# S04-INTERFACES.net
KiCad netlist of a schematic drawn in Altium Designer
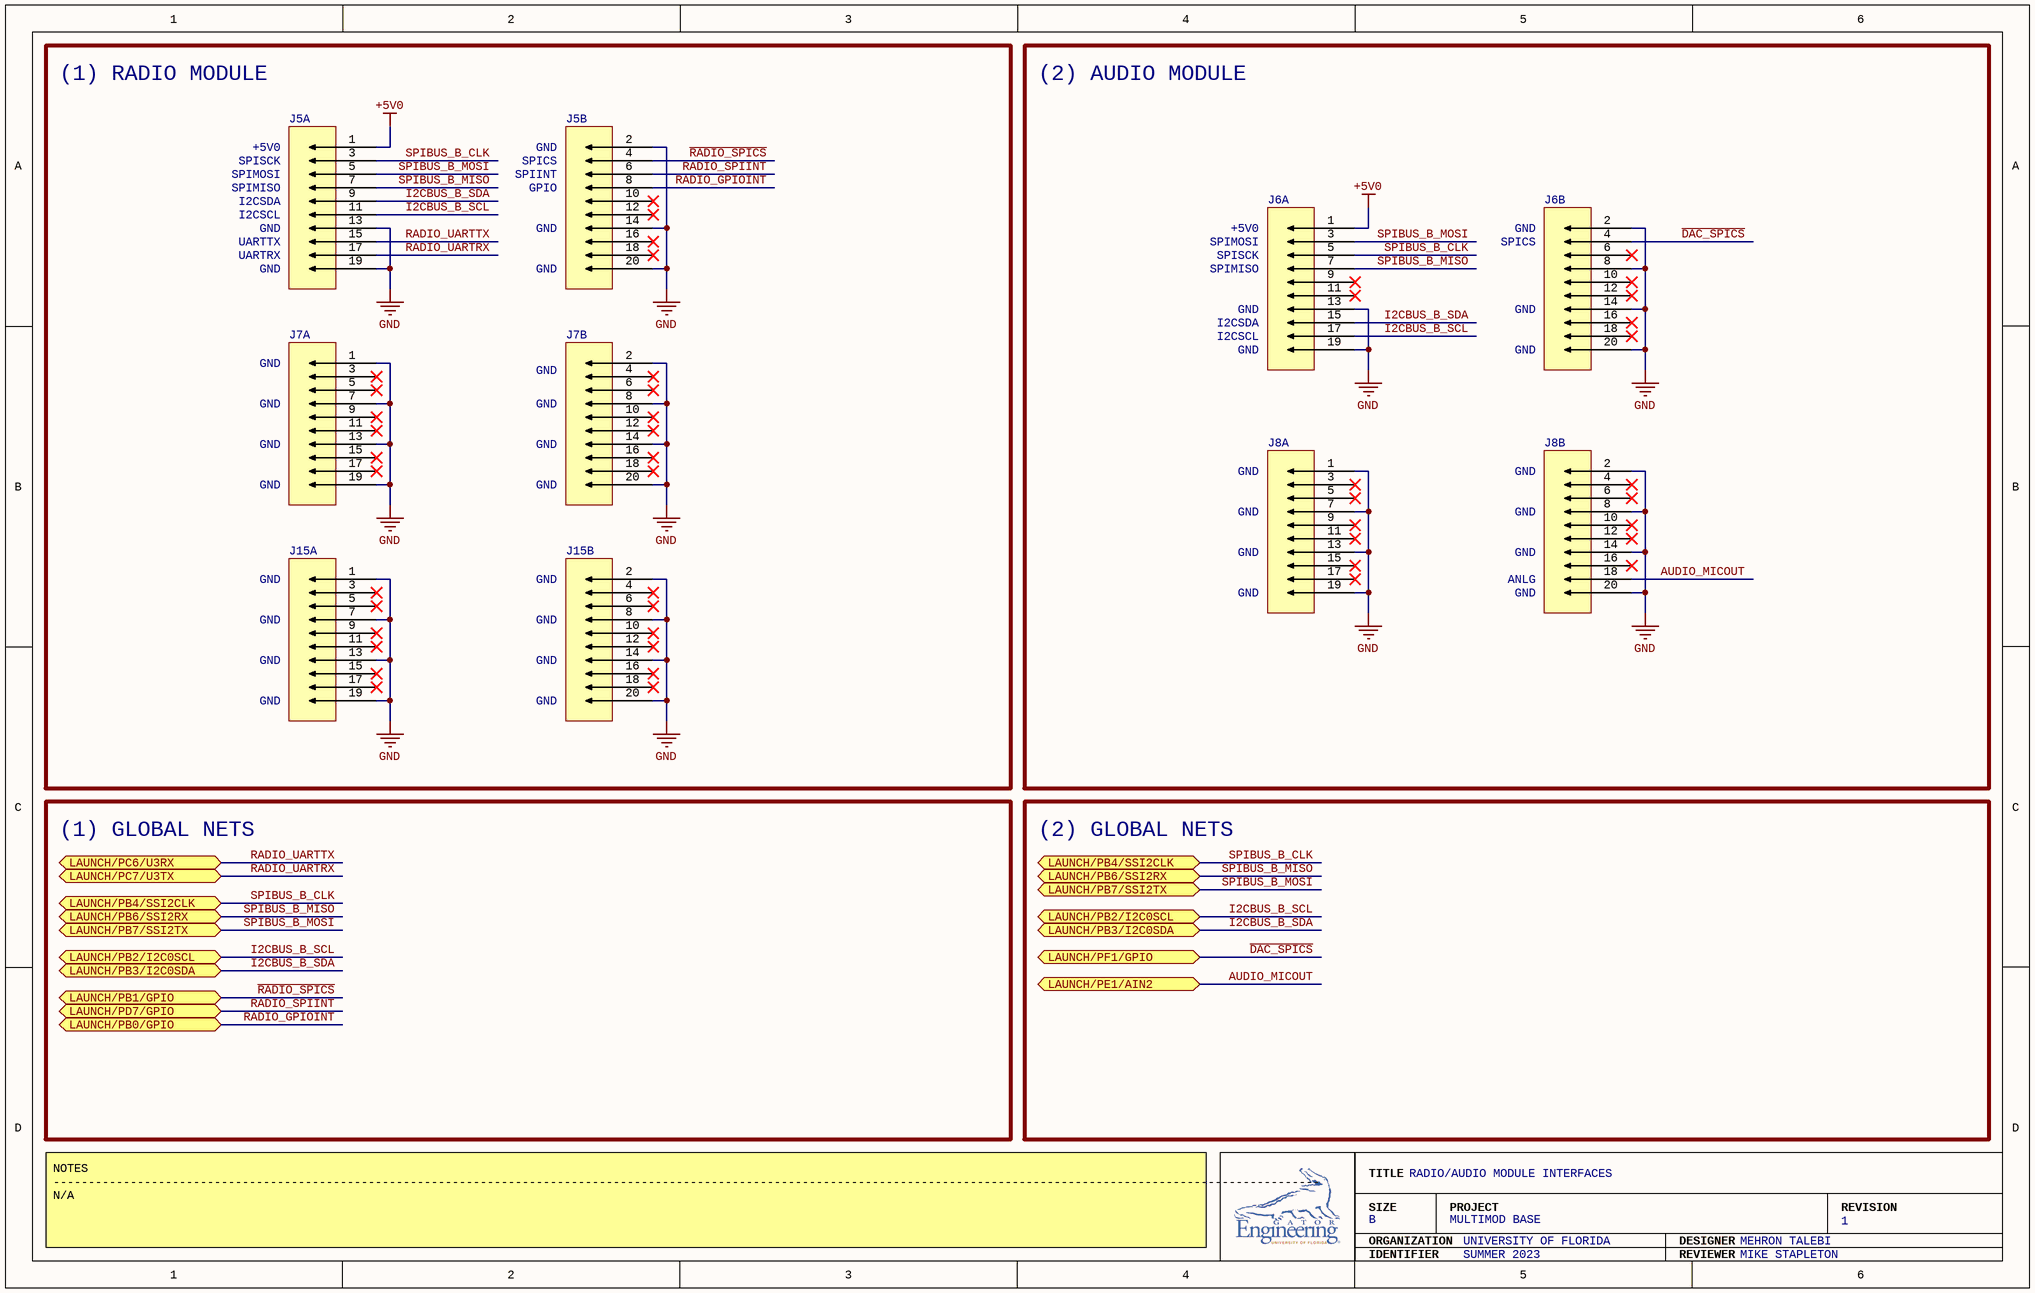
[diagram p0: S04-INTERFACES.SchDoc]

(export (version "E")
  (design (tool "Eeschema 10.0.6"))
  (components
    (comp (ref "J5")
      (value "95278-101-20LF")
      (footprint "95278-101-20LF")
      (description "CONN HEADER SMD 20POS 2.54MM")
      (libsource (lib "Master") (part "95278-101-20LF"))
    )
    (comp (ref "J6")
      (value "95278-101-20LF")
      (footprint "95278-101-20LF")
      (description "CONN HEADER SMD 20POS 2.54MM")
      (libsource (lib "Master") (part "95278-101-20LF"))
    )
    (comp (ref "J7")
      (value "95278-101-20LF")
      (footprint "95278-101-20LF")
      (description "CONN HEADER SMD 20POS 2.54MM")
      (libsource (lib "Master") (part "95278-101-20LF"))
    )
    (comp (ref "J8")
      (value "95278-101-20LF")
      (footprint "95278-101-20LF")
      (description "CONN HEADER SMD 20POS 2.54MM")
      (libsource (lib "Master") (part "95278-101-20LF"))
    )
    (comp (ref "J15")
      (value "95278-101-20LF")
      (footprint "95278-101-20LF")
      (description "CONN HEADER SMD 20POS 2.54MM")
      (libsource (lib "Master") (part "95278-101-20LF"))
    )
  )
  (nets
    (net (code "1") (name "+5V0") (class "Default")
      (node (ref "J5") (pin "1") (pinfunction "1_1") (pintype "passive"))
      (node (ref "J6") (pin "1") (pinfunction "1_1") (pintype "passive"))
    )
    (net (code "2") (name "/AUDIO_MICOUT") (class "Default")
      (node (ref "J8") (pin "18") (pinfunction "18_18") (pintype "passive"))
    )
    (net (code "3") (name "/DAC_SPICS") (class "Default")
      (node (ref "J6") (pin "4") (pinfunction "4_4") (pintype "passive"))
    )
    (net (code "4") (name "/I2CBUS_B_SCL") (class "Default")
      (node (ref "J5") (pin "11") (pinfunction "11_11") (pintype "passive"))
      (node (ref "J6") (pin "17") (pinfunction "17_17") (pintype "passive"))
    )
    (net (code "5") (name "/I2CBUS_B_SDA") (class "Default")
      (node (ref "J5") (pin "9") (pinfunction "9_9") (pintype "passive"))
      (node (ref "J6") (pin "15") (pinfunction "15_15") (pintype "passive"))
    )
    (net (code "6") (name "/RADIO_GPIOINT") (class "Default")
      (node (ref "J5") (pin "8") (pinfunction "8_8") (pintype "passive"))
    )
    (net (code "7") (name "/RADIO_SPICS") (class "Default")
      (node (ref "J5") (pin "4") (pinfunction "4_4") (pintype "passive"))
    )
    (net (code "8") (name "/RADIO_SPIINT") (class "Default")
      (node (ref "J5") (pin "6") (pinfunction "6_6") (pintype "passive"))
    )
    (net (code "9") (name "/RADIO_UARTRX") (class "Default")
      (node (ref "J5") (pin "17") (pinfunction "17_17") (pintype "passive"))
    )
    (net (code "10") (name "/RADIO_UARTTX") (class "Default")
      (node (ref "J5") (pin "15") (pinfunction "15_15") (pintype "passive"))
    )
    (net (code "11") (name "/SPIBUS_B_CLK") (class "Default")
      (node (ref "J5") (pin "3") (pinfunction "3_3") (pintype "passive"))
      (node (ref "J6") (pin "5") (pinfunction "5_5") (pintype "passive"))
    )
    (net (code "12") (name "/SPIBUS_B_MISO") (class "Default")
      (node (ref "J5") (pin "7") (pinfunction "7_7") (pintype "passive"))
      (node (ref "J6") (pin "7") (pinfunction "7_7") (pintype "passive"))
    )
    (net (code "13") (name "/SPIBUS_B_MOSI") (class "Default")
      (node (ref "J5") (pin "5") (pinfunction "5_5") (pintype "passive"))
      (node (ref "J6") (pin "3") (pinfunction "3_3") (pintype "passive"))
    )
    (net (code "14") (name "GND") (class "Default")
      (node (ref "J15") (pin "1") (pinfunction "1_1") (pintype "passive"))
      (node (ref "J15") (pin "13") (pinfunction "13_13") (pintype "passive"))
      (node (ref "J15") (pin "14") (pinfunction "14_14") (pintype "passive"))
      (node (ref "J15") (pin "19") (pinfunction "19_19") (pintype "passive"))
      (node (ref "J15") (pin "2") (pinfunction "2_2") (pintype "passive"))
      (node (ref "J15") (pin "20") (pinfunction "20_20") (pintype "passive"))
      (node (ref "J15") (pin "7") (pinfunction "7_7") (pintype "passive"))
      (node (ref "J15") (pin "8") (pinfunction "8_8") (pintype "passive"))
      (node (ref "J5") (pin "13") (pinfunction "13_13") (pintype "passive"))
      (node (ref "J5") (pin "14") (pinfunction "14_14") (pintype "passive"))
      (node (ref "J5") (pin "19") (pinfunction "19_19") (pintype "passive"))
      (node (ref "J5") (pin "2") (pinfunction "2_2") (pintype "passive"))
      (node (ref "J5") (pin "20") (pinfunction "20_20") (pintype "passive"))
      (node (ref "J6") (pin "13") (pinfunction "13_13") (pintype "passive"))
      (node (ref "J6") (pin "14") (pinfunction "14_14") (pintype "passive"))
      (node (ref "J6") (pin "19") (pinfunction "19_19") (pintype "passive"))
      (node (ref "J6") (pin "2") (pinfunction "2_2") (pintype "passive"))
      (node (ref "J6") (pin "20") (pinfunction "20_20") (pintype "passive"))
      (node (ref "J6") (pin "8") (pinfunction "8_8") (pintype "passive"))
      (node (ref "J7") (pin "1") (pinfunction "1_1") (pintype "passive"))
      (node (ref "J7") (pin "13") (pinfunction "13_13") (pintype "passive"))
      (node (ref "J7") (pin "14") (pinfunction "14_14") (pintype "passive"))
      (node (ref "J7") (pin "19") (pinfunction "19_19") (pintype "passive"))
      (node (ref "J7") (pin "2") (pinfunction "2_2") (pintype "passive"))
      (node (ref "J7") (pin "20") (pinfunction "20_20") (pintype "passive"))
      (node (ref "J7") (pin "7") (pinfunction "7_7") (pintype "passive"))
      (node (ref "J7") (pin "8") (pinfunction "8_8") (pintype "passive"))
      (node (ref "J8") (pin "1") (pinfunction "1_1") (pintype "passive"))
      (node (ref "J8") (pin "13") (pinfunction "13_13") (pintype "passive"))
      (node (ref "J8") (pin "14") (pinfunction "14_14") (pintype "passive"))
      (node (ref "J8") (pin "19") (pinfunction "19_19") (pintype "passive"))
      (node (ref "J8") (pin "2") (pinfunction "2_2") (pintype "passive"))
      (node (ref "J8") (pin "20") (pinfunction "20_20") (pintype "passive"))
      (node (ref "J8") (pin "7") (pinfunction "7_7") (pintype "passive"))
      (node (ref "J8") (pin "8") (pinfunction "8_8") (pintype "passive"))
    )
    (net (code "15") (name "unconnected-(J5-Pad10)") (class "Default")
      (node (ref "J5") (pin "10") (pinfunction "10_10") (pintype "passive+no_connect"))
    )
    (net (code "16") (name "unconnected-(J5-Pad12)") (class "Default")
      (node (ref "J5") (pin "12") (pinfunction "12_12") (pintype "passive+no_connect"))
    )
    (net (code "17") (name "unconnected-(J5-Pad16)") (class "Default")
      (node (ref "J5") (pin "16") (pinfunction "16_16") (pintype "passive+no_connect"))
    )
    (net (code "18") (name "unconnected-(J5-Pad18)") (class "Default")
      (node (ref "J5") (pin "18") (pinfunction "18_18") (pintype "passive+no_connect"))
    )
    (net (code "19") (name "unconnected-(J6-Pad6)") (class "Default")
      (node (ref "J6") (pin "6") (pinfunction "6_6") (pintype "passive+no_connect"))
    )
    (net (code "20") (name "unconnected-(J6-Pad9)") (class "Default")
      (node (ref "J6") (pin "9") (pinfunction "9_9") (pintype "passive+no_connect"))
    )
    (net (code "21") (name "unconnected-(J6-Pad10)") (class "Default")
      (node (ref "J6") (pin "10") (pinfunction "10_10") (pintype "passive+no_connect"))
    )
    (net (code "22") (name "unconnected-(J6-Pad11)") (class "Default")
      (node (ref "J6") (pin "11") (pinfunction "11_11") (pintype "passive+no_connect"))
    )
    (net (code "23") (name "unconnected-(J6-Pad12)") (class "Default")
      (node (ref "J6") (pin "12") (pinfunction "12_12") (pintype "passive+no_connect"))
    )
    (net (code "24") (name "unconnected-(J6-Pad16)") (class "Default")
      (node (ref "J6") (pin "16") (pinfunction "16_16") (pintype "passive+no_connect"))
    )
    (net (code "25") (name "unconnected-(J6-Pad18)") (class "Default")
      (node (ref "J6") (pin "18") (pinfunction "18_18") (pintype "passive+no_connect"))
    )
    (net (code "26") (name "unconnected-(J7-Pad3)") (class "Default")
      (node (ref "J7") (pin "3") (pinfunction "3_3") (pintype "passive+no_connect"))
    )
    (net (code "27") (name "unconnected-(J7-Pad4)") (class "Default")
      (node (ref "J7") (pin "4") (pinfunction "4_4") (pintype "passive+no_connect"))
    )
    (net (code "28") (name "unconnected-(J7-Pad5)") (class "Default")
      (node (ref "J7") (pin "5") (pinfunction "5_5") (pintype "passive+no_connect"))
    )
    (net (code "29") (name "unconnected-(J7-Pad6)") (class "Default")
      (node (ref "J7") (pin "6") (pinfunction "6_6") (pintype "passive+no_connect"))
    )
    (net (code "30") (name "unconnected-(J7-Pad9)") (class "Default")
      (node (ref "J7") (pin "9") (pinfunction "9_9") (pintype "passive+no_connect"))
    )
    (net (code "31") (name "unconnected-(J7-Pad10)") (class "Default")
      (node (ref "J7") (pin "10") (pinfunction "10_10") (pintype "passive+no_connect"))
    )
    (net (code "32") (name "unconnected-(J7-Pad11)") (class "Default")
      (node (ref "J7") (pin "11") (pinfunction "11_11") (pintype "passive+no_connect"))
    )
    (net (code "33") (name "unconnected-(J7-Pad12)") (class "Default")
      (node (ref "J7") (pin "12") (pinfunction "12_12") (pintype "passive+no_connect"))
    )
    (net (code "34") (name "unconnected-(J7-Pad15)") (class "Default")
      (node (ref "J7") (pin "15") (pinfunction "15_15") (pintype "passive+no_connect"))
    )
    (net (code "35") (name "unconnected-(J7-Pad16)") (class "Default")
      (node (ref "J7") (pin "16") (pinfunction "16_16") (pintype "passive+no_connect"))
    )
    (net (code "36") (name "unconnected-(J7-Pad17)") (class "Default")
      (node (ref "J7") (pin "17") (pinfunction "17_17") (pintype "passive+no_connect"))
    )
    (net (code "37") (name "unconnected-(J7-Pad18)") (class "Default")
      (node (ref "J7") (pin "18") (pinfunction "18_18") (pintype "passive+no_connect"))
    )
    (net (code "38") (name "unconnected-(J8-Pad3)") (class "Default")
      (node (ref "J8") (pin "3") (pinfunction "3_3") (pintype "passive+no_connect"))
    )
    (net (code "39") (name "unconnected-(J8-Pad4)") (class "Default")
      (node (ref "J8") (pin "4") (pinfunction "4_4") (pintype "passive+no_connect"))
    )
    (net (code "40") (name "unconnected-(J8-Pad5)") (class "Default")
      (node (ref "J8") (pin "5") (pinfunction "5_5") (pintype "passive+no_connect"))
    )
    (net (code "41") (name "unconnected-(J8-Pad6)") (class "Default")
      (node (ref "J8") (pin "6") (pinfunction "6_6") (pintype "passive+no_connect"))
    )
    (net (code "42") (name "unconnected-(J8-Pad9)") (class "Default")
      (node (ref "J8") (pin "9") (pinfunction "9_9") (pintype "passive+no_connect"))
    )
    (net (code "43") (name "unconnected-(J8-Pad10)") (class "Default")
      (node (ref "J8") (pin "10") (pinfunction "10_10") (pintype "passive+no_connect"))
    )
    (net (code "44") (name "unconnected-(J8-Pad11)") (class "Default")
      (node (ref "J8") (pin "11") (pinfunction "11_11") (pintype "passive+no_connect"))
    )
    (net (code "45") (name "unconnected-(J8-Pad12)") (class "Default")
      (node (ref "J8") (pin "12") (pinfunction "12_12") (pintype "passive+no_connect"))
    )
    (net (code "46") (name "unconnected-(J8-Pad15)") (class "Default")
      (node (ref "J8") (pin "15") (pinfunction "15_15") (pintype "passive+no_connect"))
    )
    (net (code "47") (name "unconnected-(J8-Pad16)") (class "Default")
      (node (ref "J8") (pin "16") (pinfunction "16_16") (pintype "passive+no_connect"))
    )
    (net (code "48") (name "unconnected-(J8-Pad17)") (class "Default")
      (node (ref "J8") (pin "17") (pinfunction "17_17") (pintype "passive+no_connect"))
    )
    (net (code "49") (name "unconnected-(J15-Pad3)") (class "Default")
      (node (ref "J15") (pin "3") (pinfunction "3_3") (pintype "passive+no_connect"))
    )
    (net (code "50") (name "unconnected-(J15-Pad4)") (class "Default")
      (node (ref "J15") (pin "4") (pinfunction "4_4") (pintype "passive+no_connect"))
    )
    (net (code "51") (name "unconnected-(J15-Pad5)") (class "Default")
      (node (ref "J15") (pin "5") (pinfunction "5_5") (pintype "passive+no_connect"))
    )
    (net (code "52") (name "unconnected-(J15-Pad6)") (class "Default")
      (node (ref "J15") (pin "6") (pinfunction "6_6") (pintype "passive+no_connect"))
    )
    (net (code "53") (name "unconnected-(J15-Pad9)") (class "Default")
      (node (ref "J15") (pin "9") (pinfunction "9_9") (pintype "passive+no_connect"))
    )
    (net (code "54") (name "unconnected-(J15-Pad10)") (class "Default")
      (node (ref "J15") (pin "10") (pinfunction "10_10") (pintype "passive+no_connect"))
    )
    (net (code "55") (name "unconnected-(J15-Pad11)") (class "Default")
      (node (ref "J15") (pin "11") (pinfunction "11_11") (pintype "passive+no_connect"))
    )
    (net (code "56") (name "unconnected-(J15-Pad12)") (class "Default")
      (node (ref "J15") (pin "12") (pinfunction "12_12") (pintype "passive+no_connect"))
    )
    (net (code "57") (name "unconnected-(J15-Pad15)") (class "Default")
      (node (ref "J15") (pin "15") (pinfunction "15_15") (pintype "passive+no_connect"))
    )
    (net (code "58") (name "unconnected-(J15-Pad16)") (class "Default")
      (node (ref "J15") (pin "16") (pinfunction "16_16") (pintype "passive+no_connect"))
    )
    (net (code "59") (name "unconnected-(J15-Pad17)") (class "Default")
      (node (ref "J15") (pin "17") (pinfunction "17_17") (pintype "passive+no_connect"))
    )
    (net (code "60") (name "unconnected-(J15-Pad18)") (class "Default")
      (node (ref "J15") (pin "18") (pinfunction "18_18") (pintype "passive+no_connect"))
    )
  )
)
